# esp32.net
KiCad netlist of a schematic drawn in EAGLE
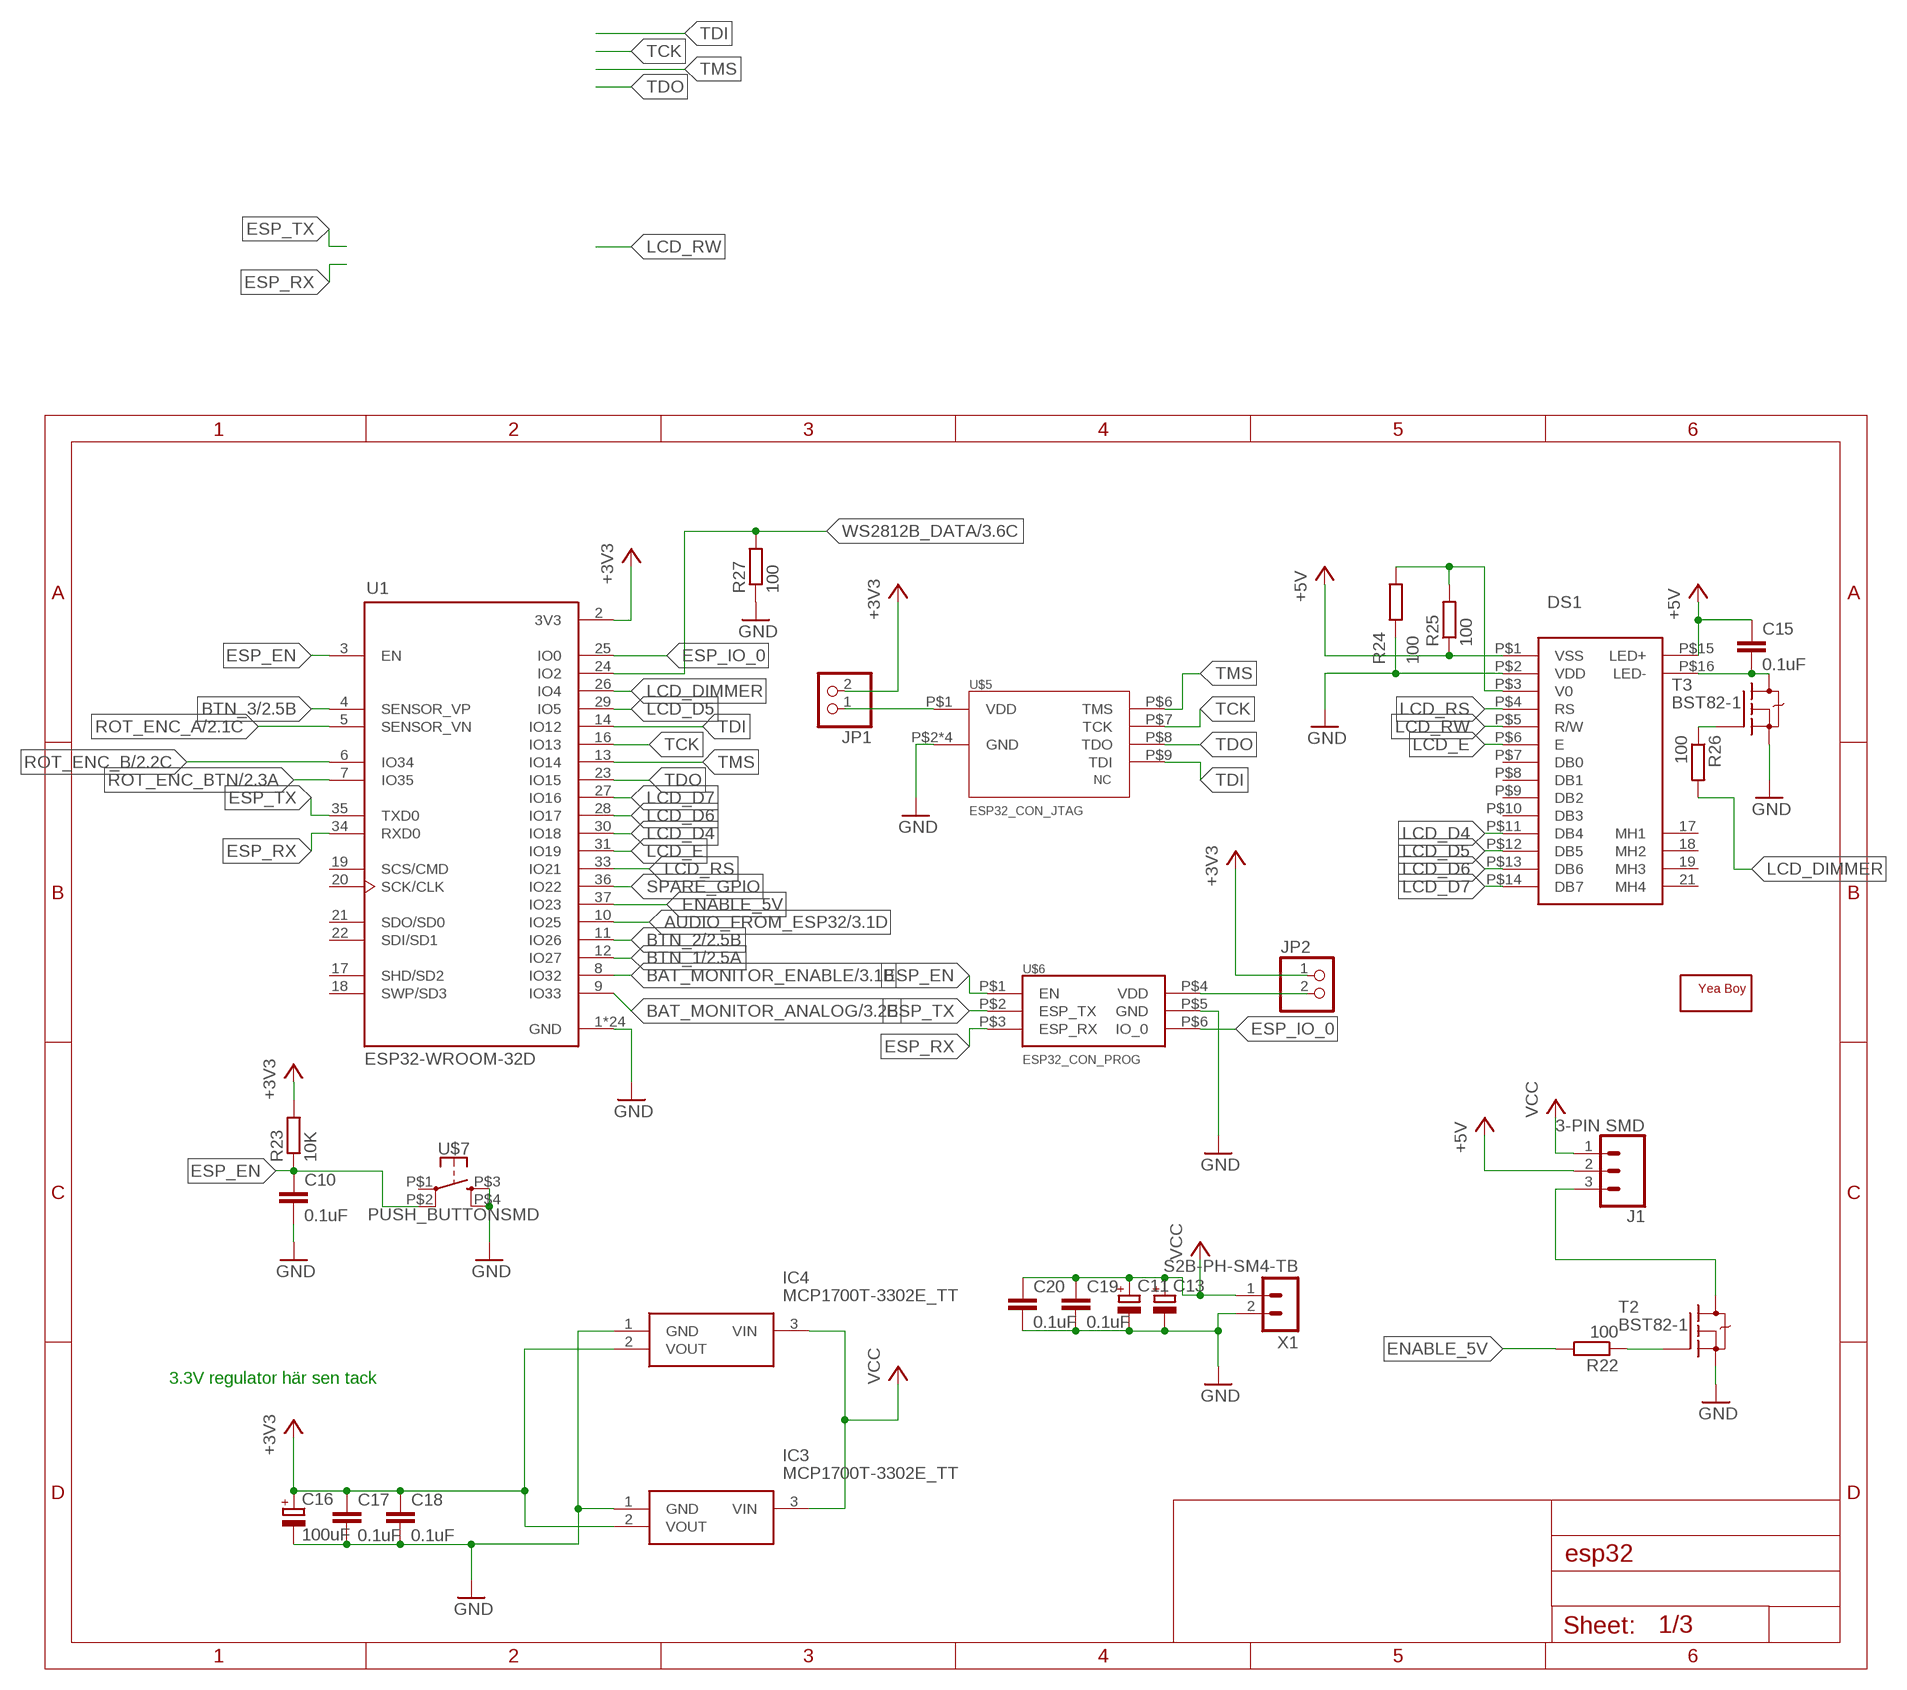
[diagram p0: schematic, sheet 1]
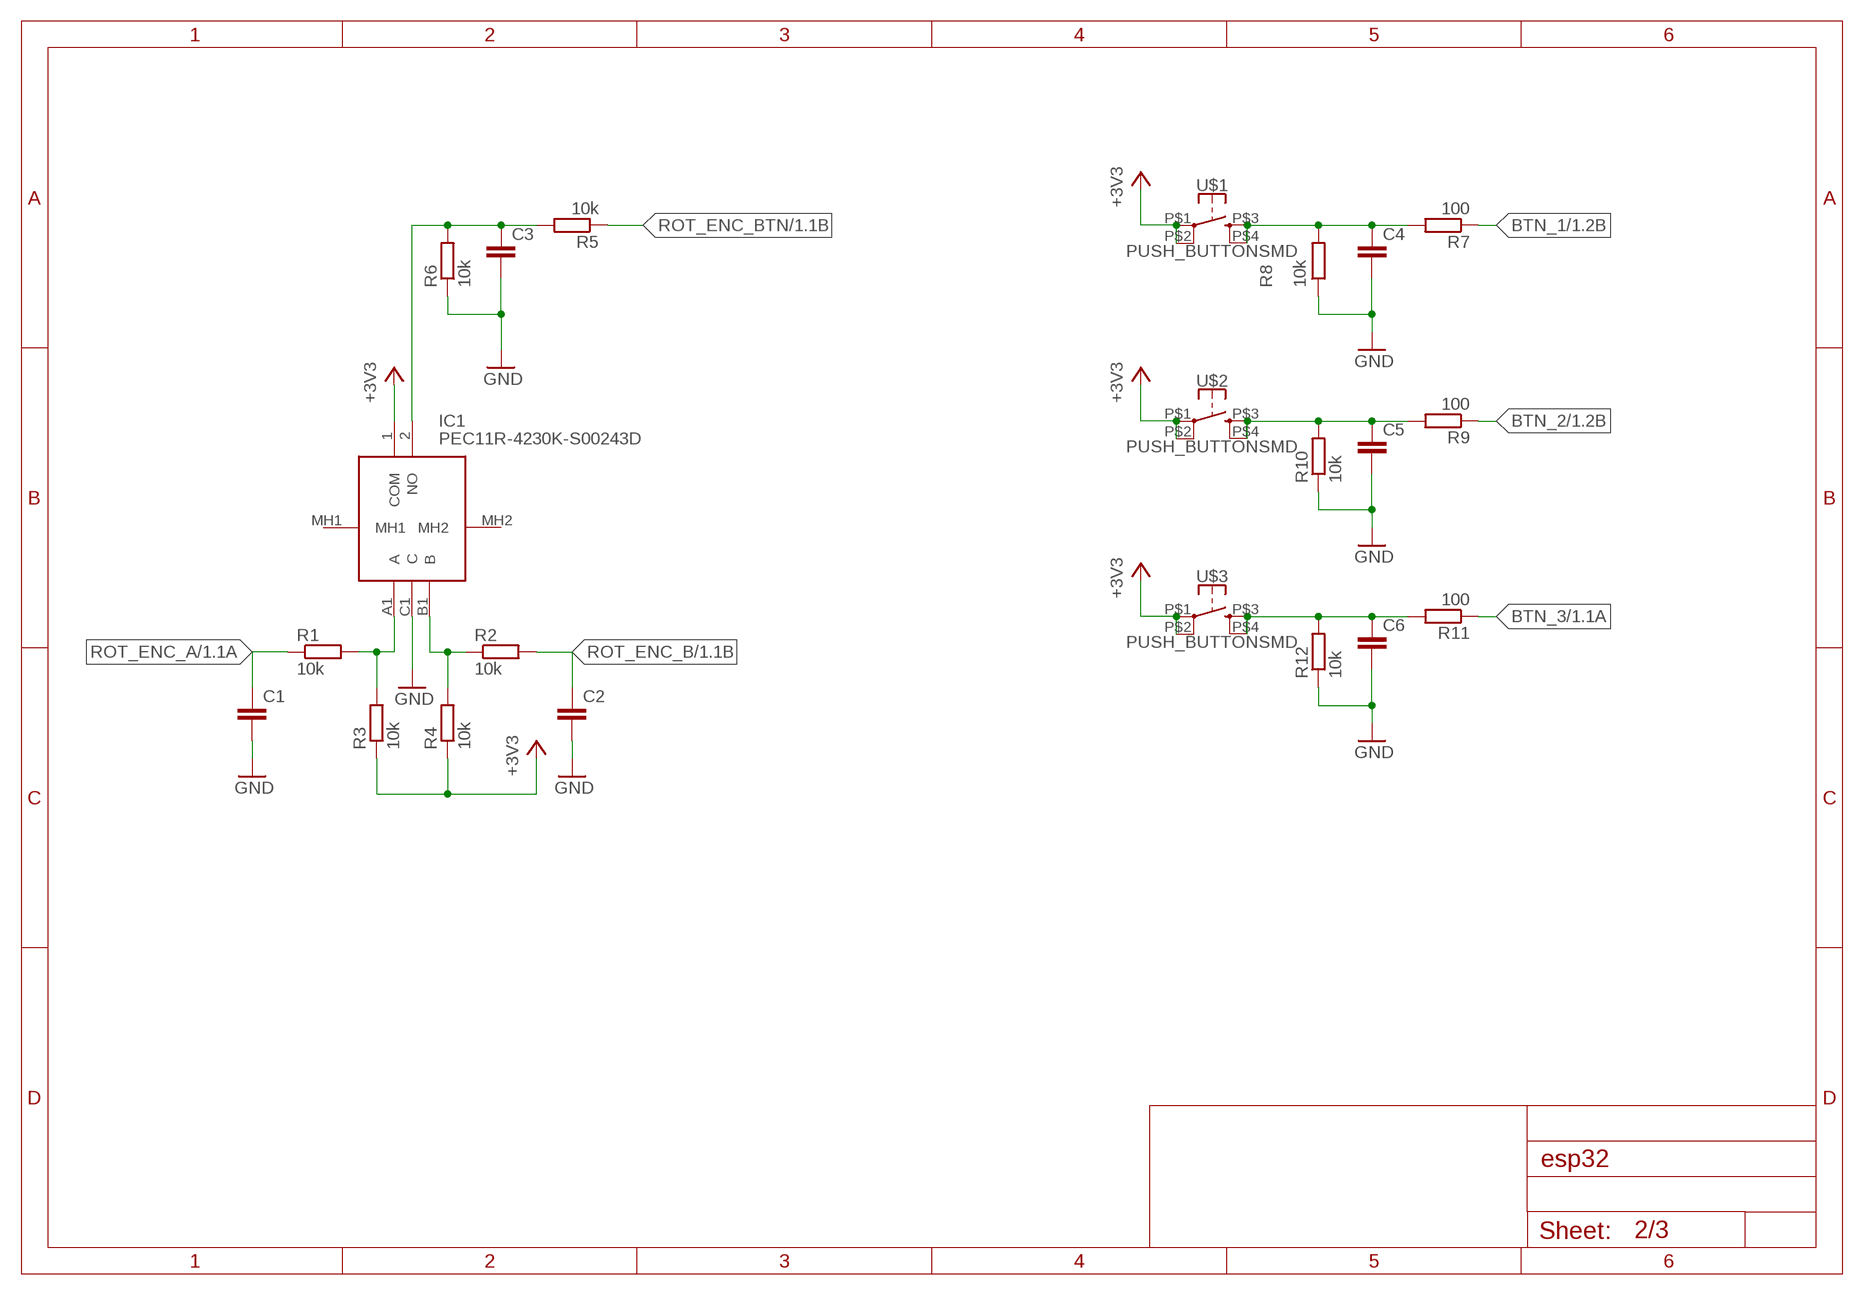
[diagram p1: schematic, sheet 2]
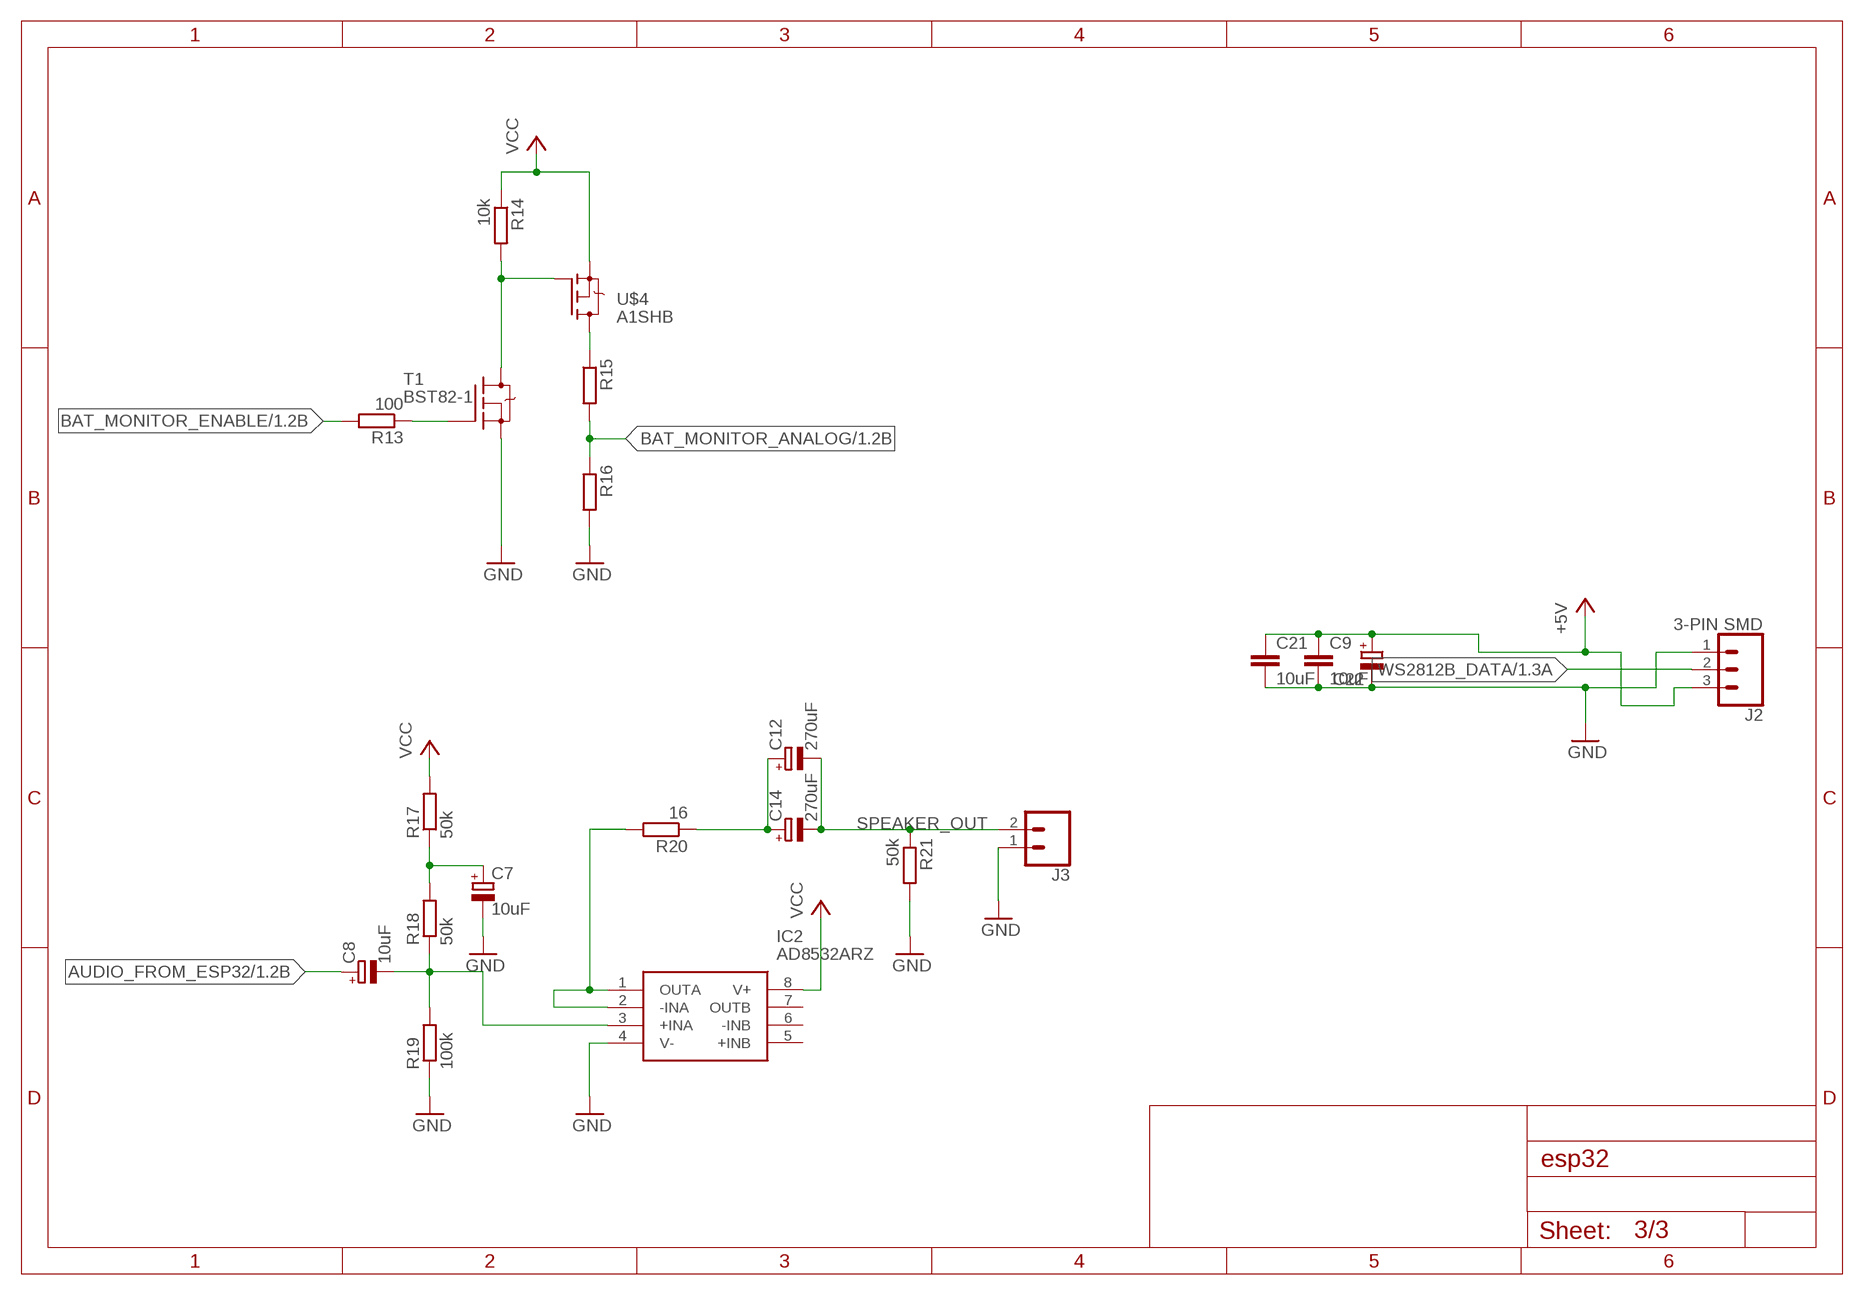
[diagram p2: schematic, sheet 3]

(export (version "E")
  (design (tool "Eeschema 10.0.6"))
  (components
    (comp (ref "C10")
      (value "0.1uF")
      (footprint "eagle-import:C0603")
      (libsource (lib "eagle-import") (part "C-EUC0603"))
    )
    (comp (ref "C11")
      (value "CPOL-EU153CLV-0605")
      (footprint "eagle-import:153CLV-0605")
      (libsource (lib "eagle-import") (part "CPOL-EU153CLV-0605"))
    )
    (comp (ref "C13")
      (value "CPOL-EU153CLV-0505")
      (footprint "eagle-import:153CLV-0505")
      (libsource (lib "eagle-import") (part "CPOL-EU153CLV-0505"))
    )
    (comp (ref "C15")
      (value "0.1uF")
      (footprint "eagle-import:C0603")
      (libsource (lib "eagle-import") (part "C-EUC0603"))
    )
    (comp (ref "C16")
      (value "100uF")
      (footprint "eagle-import:153CLV-0605")
      (libsource (lib "eagle-import") (part "CPOL-EU153CLV-0605"))
    )
    (comp (ref "C17")
      (value "0.1uF")
      (footprint "eagle-import:C0603")
      (libsource (lib "eagle-import") (part "C-EUC0603"))
    )
    (comp (ref "C18")
      (value "0.1uF")
      (footprint "eagle-import:C0603")
      (libsource (lib "eagle-import") (part "C-EUC0603"))
    )
    (comp (ref "C19")
      (value "0.1uF")
      (footprint "eagle-import:C0603")
      (libsource (lib "eagle-import") (part "C-EUC0603"))
    )
    (comp (ref "C20")
      (value "0.1uF")
      (footprint "eagle-import:C0603")
      (libsource (lib "eagle-import") (part "C-EUC0603"))
    )
    (comp (ref "DS1")
      (value "NHD-0216XZ-FSW-GBWSMT")
      (footprint "eagle-import:NHD0216XZFSWGBW_SMT")
      (libsource (lib "eagle-import") (part "NHD-0216XZ-FSW-GBWSMT"))
    )
    (comp (ref "IC3")
      (value "MCP1700T-3302E_TT")
      (footprint "eagle-import:SOT95P237X112-3N")
      (fields
        (field (name "MANUFACTURER_PART_NUMBER") "MCP1700T-3302E/TT")
        (field (name "MOUSER_PART_NUMBER") "579-MCP1700T3302E/TT")
      )
      (libsource (lib "eagle-import") (part "MCP1700T-3302E_TT"))
    )
    (comp (ref "IC4")
      (value "MCP1700T-3302E_TT")
      (footprint "eagle-import:SOT95P237X112-3N")
      (fields
        (field (name "MANUFACTURER_PART_NUMBER") "MCP1700T-3302E/TT")
        (field (name "MOUSER_PART_NUMBER") "579-MCP1700T3302E/TT")
      )
      (libsource (lib "eagle-import") (part "MCP1700T-3302E_TT"))
    )
    (comp (ref "J1")
      (value "3-PIN SMD")
      (footprint "eagle-import:JST-3-SMD")
      (libsource (lib "eagle-import") (part "CONN_03JST-SMD"))
    )
    (comp (ref "JP1")
      (value "PINHD-1X2")
      (footprint "eagle-import:1X02")
      (libsource (lib "eagle-import") (part "PINHD-1X2"))
    )
    (comp (ref "JP2")
      (value "PINHD-1X2")
      (footprint "eagle-import:1X02")
      (libsource (lib "eagle-import") (part "PINHD-1X2"))
    )
    (comp (ref "R22")
      (value "100")
      (footprint "eagle-import:R0603")
      (libsource (lib "eagle-import") (part "R-EU_R0603"))
    )
    (comp (ref "R23")
      (value "10K")
      (footprint "eagle-import:R0603")
      (libsource (lib "eagle-import") (part "R-EU_R0603"))
    )
    (comp (ref "R24")
      (value "100")
      (footprint "eagle-import:R0603")
      (libsource (lib "eagle-import") (part "R-EU_R0603"))
    )
    (comp (ref "R25")
      (value "100")
      (footprint "eagle-import:R0603")
      (libsource (lib "eagle-import") (part "R-EU_R0603"))
    )
    (comp (ref "R26")
      (value "100")
      (footprint "eagle-import:R0603")
      (libsource (lib "eagle-import") (part "R-EU_R0603"))
    )
    (comp (ref "R27")
      (value "100")
      (footprint "eagle-import:R0603")
      (libsource (lib "eagle-import") (part "R-EU_R0603"))
    )
    (comp (ref "T2")
      (value "BST82-1")
      (footprint "eagle-import:SOT23")
      (libsource (lib "eagle-import") (part "BST82-1"))
    )
    (comp (ref "T3")
      (value "BST82-1")
      (footprint "eagle-import:SOT23")
      (libsource (lib "eagle-import") (part "BST82-1"))
    )
    (comp (ref "U$5")
      (value "ESP32_CON_JTAG")
      (footprint "eagle-import:DC3_10P_0.05")
      (libsource (lib "eagle-import") (part "ESP32_CON_JTAG"))
    )
    (comp (ref "U$6")
      (value "ESP32_CON_PROG")
      (footprint "eagle-import:DC3_6P_0.05")
      (libsource (lib "eagle-import") (part "ESP32_CON_PROG"))
    )
    (comp (ref "U$7")
      (value "PUSH_BUTTONSMD")
      (footprint "eagle-import:TACTILE_SWITCH_PTH_6.0MM_SMD")
      (libsource (lib "eagle-import") (part "PUSH_BUTTONSMD"))
    )
    (comp (ref "U$8")
      (value "TOUCHMARK")
      (footprint "eagle-import:TOUCHMARK")
      (libsource (lib "eagle-import") (part "TOUCHMARK"))
    )
    (comp (ref "U1")
      (value "ESP32-WROOM-32D")
      (footprint "eagle-import:MODULE_ESP32-WROOM-32D")
      (fields (field (name "MANUFACTURER") "Espressif Systems"))
      (libsource (lib "eagle-import") (part "ESP32-WROOM-32D"))
    )
    (comp (ref "X1")
      (value "S2B-PH-SM4-TB")
      (footprint "eagle-import:S2B-PH-SM4-TB")
      (libsource (lib "eagle-import") (part "S2B-PH-SM4-TB"))
    )
    (comp (ref "C7")
      (value "10uF")
      (footprint "eagle-import:153CLV-0505")
      (libsource (lib "eagle-import") (part "CPOL-EU153CLV-0505"))
    )
    (comp (ref "C8")
      (value "10uF")
      (footprint "eagle-import:153CLV-0505")
      (libsource (lib "eagle-import") (part "CPOL-EU153CLV-0505"))
    )
    (comp (ref "C9")
      (value "10uF")
      (footprint "eagle-import:C0603")
      (libsource (lib "eagle-import") (part "C-EUC0603"))
    )
    (comp (ref "C12")
      (value "270uF")
      (footprint "eagle-import:153CLV-0605")
      (libsource (lib "eagle-import") (part "CPOL-EU153CLV-0605"))
    )
    (comp (ref "C14")
      (value "270uF")
      (footprint "eagle-import:153CLV-0605")
      (libsource (lib "eagle-import") (part "CPOL-EU153CLV-0605"))
    )
    (comp (ref "C21")
      (value "10uF")
      (footprint "eagle-import:C0603")
      (libsource (lib "eagle-import") (part "C-EUC0603"))
    )
    (comp (ref "C22")
      (value "CPOL-EU153CLV-0605")
      (footprint "eagle-import:153CLV-0605")
      (libsource (lib "eagle-import") (part "CPOL-EU153CLV-0605"))
    )
    (comp (ref "IC2")
      (value "AD8532ARZ")
      (footprint "eagle-import:SOIC127P600X175-8N")
      (fields (field (name "MOUSER_PART_NUMBER") "584-AD8532ARZ"))
      (libsource (lib "eagle-import") (part "AD8532ARZ"))
    )
    (comp (ref "J2")
      (value "3-PIN SMD")
      (footprint "eagle-import:JST-3-SMD")
      (libsource (lib "eagle-import") (part "CONN_03JST-SMD"))
    )
    (comp (ref "J3")
      (value "CONN_02-JST-2MM-SMT")
      (footprint "eagle-import:JST-2-SMD")
      (libsource (lib "eagle-import") (part "CONN_02-JST-2MM-SMT"))
    )
    (comp (ref "R13")
      (value "100")
      (footprint "eagle-import:R0603")
      (libsource (lib "eagle-import") (part "R-EU_R0603"))
    )
    (comp (ref "R14")
      (value "10k")
      (footprint "eagle-import:R0603")
      (libsource (lib "eagle-import") (part "R-EU_R0603"))
    )
    (comp (ref "R15")
      (value "R-EU_R0603")
      (footprint "eagle-import:R0603")
      (libsource (lib "eagle-import") (part "R-EU_R0603"))
    )
    (comp (ref "R16")
      (value "R-EU_R0603")
      (footprint "eagle-import:R0603")
      (libsource (lib "eagle-import") (part "R-EU_R0603"))
    )
    (comp (ref "R17")
      (value "50k")
      (footprint "eagle-import:R0603")
      (libsource (lib "eagle-import") (part "R-EU_R0603"))
    )
    (comp (ref "R18")
      (value "50k")
      (footprint "eagle-import:R0603")
      (libsource (lib "eagle-import") (part "R-EU_R0603"))
    )
    (comp (ref "R19")
      (value "100k")
      (footprint "eagle-import:R0603")
      (libsource (lib "eagle-import") (part "R-EU_R0603"))
    )
    (comp (ref "R20")
      (value "16")
      (footprint "eagle-import:R0603")
      (libsource (lib "eagle-import") (part "R-EU_R0603"))
    )
    (comp (ref "R21")
      (value "50k")
      (footprint "eagle-import:R0603")
      (libsource (lib "eagle-import") (part "R-EU_R0603"))
    )
    (comp (ref "T1")
      (value "BST82-1")
      (footprint "eagle-import:SOT23")
      (libsource (lib "eagle-import") (part "BST82-1"))
    )
    (comp (ref "U$4")
      (value "A1SHB")
      (footprint "eagle-import:SOT23")
      (libsource (lib "eagle-import") (part "A1SHB"))
    )
    (comp (ref "C1")
      (value "C-EUC0603")
      (footprint "eagle-import:C0603")
      (libsource (lib "eagle-import") (part "C-EUC0603"))
    )
    (comp (ref "C2")
      (value "C-EUC0603")
      (footprint "eagle-import:C0603")
      (libsource (lib "eagle-import") (part "C-EUC0603"))
    )
    (comp (ref "C3")
      (value "C-EUC0603")
      (footprint "eagle-import:C0603")
      (libsource (lib "eagle-import") (part "C-EUC0603"))
    )
    (comp (ref "C4")
      (value "C-EUC0603")
      (footprint "eagle-import:C0603")
      (libsource (lib "eagle-import") (part "C-EUC0603"))
    )
    (comp (ref "C5")
      (value "C-EUC0603")
      (footprint "eagle-import:C0603")
      (libsource (lib "eagle-import") (part "C-EUC0603"))
    )
    (comp (ref "C6")
      (value "C-EUC0603")
      (footprint "eagle-import:C0603")
      (libsource (lib "eagle-import") (part "C-EUC0603"))
    )
    (comp (ref "IC1")
      (value "PEC11R-4230K-S00243D")
      (footprint "eagle-import:PEC11R4230KS0024")
      (libsource (lib "eagle-import") (part "PEC11R-4230K-S00243D"))
    )
    (comp (ref "R1")
      (value "10k")
      (footprint "eagle-import:R0603")
      (libsource (lib "eagle-import") (part "R-EU_R0603"))
    )
    (comp (ref "R2")
      (value "10k")
      (footprint "eagle-import:R0603")
      (libsource (lib "eagle-import") (part "R-EU_R0603"))
    )
    (comp (ref "R3")
      (value "10k")
      (footprint "eagle-import:R0603")
      (libsource (lib "eagle-import") (part "R-EU_R0603"))
    )
    (comp (ref "R4")
      (value "10k")
      (footprint "eagle-import:R0603")
      (libsource (lib "eagle-import") (part "R-EU_R0603"))
    )
    (comp (ref "R5")
      (value "10k")
      (footprint "eagle-import:R0603")
      (libsource (lib "eagle-import") (part "R-EU_R0603"))
    )
    (comp (ref "R6")
      (value "10k")
      (footprint "eagle-import:R0603")
      (libsource (lib "eagle-import") (part "R-EU_R0603"))
    )
    (comp (ref "R7")
      (value "100")
      (footprint "eagle-import:R0603")
      (libsource (lib "eagle-import") (part "R-EU_R0603"))
    )
    (comp (ref "R8")
      (value "10k")
      (footprint "eagle-import:R0603")
      (libsource (lib "eagle-import") (part "R-EU_R0603"))
    )
    (comp (ref "R9")
      (value "100")
      (footprint "eagle-import:R0603")
      (libsource (lib "eagle-import") (part "R-EU_R0603"))
    )
    (comp (ref "R10")
      (value "10k")
      (footprint "eagle-import:R0603")
      (libsource (lib "eagle-import") (part "R-EU_R0603"))
    )
    (comp (ref "R11")
      (value "100")
      (footprint "eagle-import:R0603")
      (libsource (lib "eagle-import") (part "R-EU_R0603"))
    )
    (comp (ref "R12")
      (value "10k")
      (footprint "eagle-import:R0603")
      (libsource (lib "eagle-import") (part "R-EU_R0603"))
    )
    (comp (ref "U$1")
      (value "PUSH_BUTTONSMD")
      (footprint "eagle-import:TACTILE_SWITCH_PTH_6.0MM_SMD")
      (libsource (lib "eagle-import") (part "PUSH_BUTTONSMD"))
    )
    (comp (ref "U$2")
      (value "PUSH_BUTTONSMD")
      (footprint "eagle-import:TACTILE_SWITCH_PTH_6.0MM_SMD")
      (libsource (lib "eagle-import") (part "PUSH_BUTTONSMD"))
    )
    (comp (ref "U$3")
      (value "PUSH_BUTTONSMD")
      (footprint "eagle-import:TACTILE_SWITCH_PTH_6.0MM_SMD")
      (libsource (lib "eagle-import") (part "PUSH_BUTTONSMD"))
    )
  )
  (nets
    (net (code "1") (name "+3V3") (class "Default")
      (node (ref "C16") (pin "+") (pinfunction "+_+") (pintype "passive"))
      (node (ref "C17") (pin "1") (pinfunction "1_1") (pintype "passive"))
      (node (ref "C18") (pin "1") (pinfunction "1_1") (pintype "passive"))
      (node (ref "IC1") (pin "1") (pinfunction "COM_1") (pintype "bidirectional"))
      (node (ref "IC3") (pin "2") (pinfunction "VOUT_2") (pintype "bidirectional"))
      (node (ref "IC4") (pin "2") (pinfunction "VOUT_2") (pintype "bidirectional"))
      (node (ref "JP1") (pin "2") (pinfunction "2_2") (pintype "passive"))
      (node (ref "JP2") (pin "1") (pinfunction "1_1") (pintype "passive"))
      (node (ref "R23") (pin "2") (pinfunction "2_2") (pintype "passive"))
      (node (ref "R3") (pin "1") (pinfunction "1_1") (pintype "passive"))
      (node (ref "R4") (pin "1") (pinfunction "1_1") (pintype "passive"))
      (node (ref "U$1") (pin "P$1") (pinfunction "1_P$1") (pintype "passive"))
      (node (ref "U$1") (pin "P$2") (pinfunction "2_P$2") (pintype "passive"))
      (node (ref "U$2") (pin "P$1") (pinfunction "1_P$1") (pintype "passive"))
      (node (ref "U$2") (pin "P$2") (pinfunction "2_P$2") (pintype "passive"))
      (node (ref "U$3") (pin "P$1") (pinfunction "1_P$1") (pintype "passive"))
      (node (ref "U$3") (pin "P$2") (pinfunction "2_P$2") (pintype "passive"))
      (node (ref "U1") (pin "2") (pinfunction "3V3_2") (pintype "power_in"))
    )
    (net (code "2") (name "+5V") (class "Default")
      (node (ref "C15") (pin "1") (pinfunction "1_1") (pintype "passive"))
      (node (ref "C21") (pin "1") (pinfunction "1_1") (pintype "passive"))
      (node (ref "C22") (pin "+") (pinfunction "+_+") (pintype "passive"))
      (node (ref "C9") (pin "1") (pinfunction "1_1") (pintype "passive"))
      (node (ref "DS1") (pin "P$1") (pinfunction "VSS_P$1") (pintype "bidirectional"))
      (node (ref "DS1") (pin "P$15") (pinfunction "LED+_P$15") (pintype "bidirectional"))
      (node (ref "J1") (pin "2") (pinfunction "2_2") (pintype "passive"))
      (node (ref "J2") (pin "3") (pinfunction "3_3") (pintype "passive"))
      (node (ref "R25") (pin "1") (pinfunction "1_1") (pintype "passive"))
    )
    (net (code "3") (name "AUDIO_FROM_ESP32") (class "Default")
      (node (ref "C8") (pin "+") (pinfunction "+_+") (pintype "passive"))
      (node (ref "U1") (pin "10") (pinfunction "IO25_10") (pintype "bidirectional"))
    )
    (net (code "4") (name "BAT_MONITOR_ANALOG") (class "Default")
      (node (ref "R15") (pin "2") (pinfunction "2_2") (pintype "passive"))
      (node (ref "R16") (pin "1") (pinfunction "1_1") (pintype "passive"))
      (node (ref "U1") (pin "9") (pinfunction "IO33_9") (pintype "bidirectional"))
    )
    (net (code "5") (name "BAT_MONITOR_ENABLE") (class "Default")
      (node (ref "R13") (pin "2") (pinfunction "2_2") (pintype "passive"))
      (node (ref "U1") (pin "8") (pinfunction "IO32_8") (pintype "bidirectional"))
    )
    (net (code "6") (name "BTN_1") (class "Default")
      (node (ref "R7") (pin "1") (pinfunction "1_1") (pintype "passive"))
      (node (ref "U1") (pin "12") (pinfunction "IO27_12") (pintype "bidirectional"))
    )
    (net (code "7") (name "BTN_2") (class "Default")
      (node (ref "R9") (pin "1") (pinfunction "1_1") (pintype "passive"))
      (node (ref "U1") (pin "11") (pinfunction "IO26_11") (pintype "bidirectional"))
    )
    (net (code "8") (name "BTN_3") (class "Default")
      (node (ref "R11") (pin "1") (pinfunction "1_1") (pintype "passive"))
      (node (ref "U1") (pin "4") (pinfunction "SENSOR_VP_4") (pintype "input"))
    )
    (net (code "9") (name "ENABLE_5V") (class "Default")
      (node (ref "R22") (pin "2") (pinfunction "2_2") (pintype "passive"))
      (node (ref "U1") (pin "37") (pinfunction "IO23_37") (pintype "bidirectional"))
    )
    (net (code "10") (name "ESP_EN") (class "Default")
      (node (ref "C10") (pin "1") (pinfunction "1_1") (pintype "passive"))
      (node (ref "R23") (pin "1") (pinfunction "1_1") (pintype "passive"))
      (node (ref "U$6") (pin "P$1") (pinfunction "EN_P$1") (pintype "bidirectional"))
      (node (ref "U$7") (pin "P$2") (pinfunction "2_P$2") (pintype "passive"))
      (node (ref "U1") (pin "3") (pinfunction "EN_3") (pintype "input"))
    )
    (net (code "11") (name "ESP_IO_0") (class "Default")
      (node (ref "U$6") (pin "P$6") (pinfunction "IO_0_P$6") (pintype "bidirectional"))
      (node (ref "U1") (pin "25") (pinfunction "IO0_25") (pintype "bidirectional"))
    )
    (net (code "12") (name "ESP_RX") (class "Default")
      (node (ref "U$6") (pin "P$3") (pinfunction "ESP_RX_P$3") (pintype "bidirectional"))
      (node (ref "U1") (pin "34") (pinfunction "RXD0_34") (pintype "bidirectional"))
    )
    (net (code "13") (name "ESP_TX") (class "Default")
      (node (ref "U$6") (pin "P$2") (pinfunction "ESP_TX_P$2") (pintype "bidirectional"))
      (node (ref "U1") (pin "35") (pinfunction "TXD0_35") (pintype "bidirectional"))
    )
    (net (code "14") (name "GND") (class "Default")
      (node (ref "C1") (pin "2") (pinfunction "2_2") (pintype "passive"))
      (node (ref "C10") (pin "2") (pinfunction "2_2") (pintype "passive"))
      (node (ref "C11") (pin "-") (pinfunction "-_-") (pintype "passive"))
      (node (ref "C13") (pin "-") (pinfunction "-_-") (pintype "passive"))
      (node (ref "C16") (pin "-") (pinfunction "-_-") (pintype "passive"))
      (node (ref "C17") (pin "2") (pinfunction "2_2") (pintype "passive"))
      (node (ref "C18") (pin "2") (pinfunction "2_2") (pintype "passive"))
      (node (ref "C19") (pin "2") (pinfunction "2_2") (pintype "passive"))
      (node (ref "C2") (pin "2") (pinfunction "2_2") (pintype "passive"))
      (node (ref "C20") (pin "2") (pinfunction "2_2") (pintype "passive"))
      (node (ref "C21") (pin "2") (pinfunction "2_2") (pintype "passive"))
      (node (ref "C22") (pin "-") (pinfunction "-_-") (pintype "passive"))
      (node (ref "C3") (pin "2") (pinfunction "2_2") (pintype "passive"))
      (node (ref "C4") (pin "2") (pinfunction "2_2") (pintype "passive"))
      (node (ref "C5") (pin "2") (pinfunction "2_2") (pintype "passive"))
      (node (ref "C6") (pin "2") (pinfunction "2_2") (pintype "passive"))
      (node (ref "C7") (pin "-") (pinfunction "-_-") (pintype "passive"))
      (node (ref "C9") (pin "2") (pinfunction "2_2") (pintype "passive"))
      (node (ref "DS1") (pin "P$2") (pinfunction "VDD_P$2") (pintype "bidirectional"))
      (node (ref "IC1") (pin "C1") (pinfunction "C_C1") (pintype "bidirectional"))
      (node (ref "IC2") (pin "4") (pinfunction "V-_4") (pintype "bidirectional"))
      (node (ref "IC3") (pin "1") (pinfunction "GND_1") (pintype "bidirectional"))
      (node (ref "IC4") (pin "1") (pinfunction "GND_1") (pintype "bidirectional"))
      (node (ref "J2") (pin "1") (pinfunction "1_1") (pintype "passive"))
      (node (ref "J3") (pin "1") (pinfunction "2_1") (pintype "passive"))
      (node (ref "R10") (pin "1") (pinfunction "1_1") (pintype "passive"))
      (node (ref "R12") (pin "1") (pinfunction "1_1") (pintype "passive"))
      (node (ref "R16") (pin "2") (pinfunction "2_2") (pintype "passive"))
      (node (ref "R19") (pin "1") (pinfunction "1_1") (pintype "passive"))
      (node (ref "R21") (pin "2") (pinfunction "2_2") (pintype "passive"))
      (node (ref "R24") (pin "1") (pinfunction "1_1") (pintype "passive"))
      (node (ref "R27") (pin "1") (pinfunction "1_1") (pintype "passive"))
      (node (ref "R6") (pin "1") (pinfunction "1_1") (pintype "passive"))
      (node (ref "R8") (pin "1") (pinfunction "1_1") (pintype "passive"))
      (node (ref "T1") (pin "2") (pinfunction "S_2") (pintype "passive"))
      (node (ref "T2") (pin "2") (pinfunction "S_2") (pintype "passive"))
      (node (ref "T3") (pin "2") (pinfunction "S_2") (pintype "passive"))
      (node (ref "U$5") (pin "P$2") (pinfunction "GND_P$2") (pintype "bidirectional"))
      (node (ref "U$5") (pin "P$3") (pinfunction "GND_P$3") (pintype "bidirectional"))
      (node (ref "U$5") (pin "P$4") (pinfunction "GND_P$4") (pintype "bidirectional"))
      (node (ref "U$5") (pin "P$5") (pinfunction "GND_P$5") (pintype "bidirectional"))
      (node (ref "U$6") (pin "P$5") (pinfunction "GND_P$5") (pintype "bidirectional"))
      (node (ref "U$7") (pin "P$3") (pinfunction "3_P$3") (pintype "passive"))
      (node (ref "U$7") (pin "P$4") (pinfunction "4_P$4") (pintype "passive"))
      (node (ref "U1") (pin "1") (pinfunction "GND_1") (pintype "power_in"))
      (node (ref "U1") (pin "15") (pinfunction "GND_15") (pintype "power_in"))
      (node (ref "U1") (pin "38") (pinfunction "GND_38") (pintype "power_in"))
      (node (ref "U1") (pin "39_1") (pinfunction "GND_39_1") (pintype "power_in"))
      (node (ref "U1") (pin "39_10") (pinfunction "GND_39_10") (pintype "power_in"))
      (node (ref "U1") (pin "39_11") (pinfunction "GND_39_11") (pintype "power_in"))
      (node (ref "U1") (pin "39_12") (pinfunction "GND_39_12") (pintype "power_in"))
      (node (ref "U1") (pin "39_13") (pinfunction "GND_39_13") (pintype "power_in"))
      (node (ref "U1") (pin "39_14") (pinfunction "GND_39_14") (pintype "power_in"))
      (node (ref "U1") (pin "39_15") (pinfunction "GND_39_15") (pintype "power_in"))
      (node (ref "U1") (pin "39_16") (pinfunction "GND_39_16") (pintype "power_in"))
      (node (ref "U1") (pin "39_17") (pinfunction "GND_39_17") (pintype "power_in"))
      (node (ref "U1") (pin "39_18") (pinfunction "GND_39_18") (pintype "power_in"))
      (node (ref "U1") (pin "39_19") (pinfunction "GND_39_19") (pintype "power_in"))
      (node (ref "U1") (pin "39_2") (pinfunction "GND_39_2") (pintype "power_in"))
      (node (ref "U1") (pin "39_20") (pinfunction "GND_39_20") (pintype "power_in"))
      (node (ref "U1") (pin "39_21") (pinfunction "GND_39_21") (pintype "power_in"))
      (node (ref "U1") (pin "39_3") (pinfunction "GND_39_3") (pintype "power_in"))
      (node (ref "U1") (pin "39_4") (pinfunction "GND_39_4") (pintype "power_in"))
      (node (ref "U1") (pin "39_5") (pinfunction "GND_39_5") (pintype "power_in"))
      (node (ref "U1") (pin "39_6") (pinfunction "GND_39_6") (pintype "power_in"))
      (node (ref "U1") (pin "39_7") (pinfunction "GND_39_7") (pintype "power_in"))
      (node (ref "U1") (pin "39_8") (pinfunction "GND_39_8") (pintype "power_in"))
      (node (ref "U1") (pin "39_9") (pinfunction "GND_39_9") (pintype "power_in"))
      (node (ref "X1") (pin "2") (pinfunction "2_2") (pintype "passive"))
    )
    (net (code "15") (name "LCD_D4") (class "Default")
      (node (ref "DS1") (pin "P$11") (pinfunction "DB4_P$11") (pintype "bidirectional"))
      (node (ref "U1") (pin "30") (pinfunction "IO18_30") (pintype "bidirectional"))
    )
    (net (code "16") (name "LCD_D5") (class "Default")
      (node (ref "DS1") (pin "P$12") (pinfunction "DB5_P$12") (pintype "bidirectional"))
      (node (ref "U1") (pin "29") (pinfunction "IO5_29") (pintype "bidirectional"))
    )
    (net (code "17") (name "LCD_D6") (class "Default")
      (node (ref "DS1") (pin "P$13") (pinfunction "DB6_P$13") (pintype "bidirectional"))
      (node (ref "U1") (pin "28") (pinfunction "IO17_28") (pintype "bidirectional"))
    )
    (net (code "18") (name "LCD_D7") (class "Default")
      (node (ref "DS1") (pin "P$14") (pinfunction "DB7_P$14") (pintype "bidirectional"))
      (node (ref "U1") (pin "27") (pinfunction "IO16_27") (pintype "bidirectional"))
    )
    (net (code "19") (name "LCD_DIMMER") (class "Default")
      (node (ref "R26") (pin "2") (pinfunction "2_2") (pintype "passive"))
      (node (ref "U1") (pin "26") (pinfunction "IO4_26") (pintype "bidirectional"))
    )
    (net (code "20") (name "LCD_E") (class "Default")
      (node (ref "DS1") (pin "P$6") (pinfunction "E_P$6") (pintype "bidirectional"))
      (node (ref "U1") (pin "31") (pinfunction "IO19_31") (pintype "bidirectional"))
    )
    (net (code "21") (name "LCD_RS") (class "Default")
      (node (ref "DS1") (pin "P$4") (pinfunction "RS_P$4") (pintype "bidirectional"))
      (node (ref "U1") (pin "33") (pinfunction "IO21_33") (pintype "bidirectional"))
    )
    (net (code "22") (name "LCD_RW") (class "Default")
      (node (ref "DS1") (pin "P$5") (pinfunction "R/W_P$5") (pintype "bidirectional"))
    )
    (net (code "23") (name "Net-(C7-Pad+)") (class "Default")
      (node (ref "C7") (pin "+") (pinfunction "+_+") (pintype "passive"))
      (node (ref "R17") (pin "1") (pinfunction "1_1") (pintype "passive"))
      (node (ref "R18") (pin "2") (pinfunction "2_2") (pintype "passive"))
    )
    (net (code "24") (name "Net-(C12-Pad+)") (class "Default")
      (node (ref "C12") (pin "+") (pinfunction "+_+") (pintype "passive"))
      (node (ref "C14") (pin "+") (pinfunction "+_+") (pintype "passive"))
      (node (ref "R20") (pin "1") (pinfunction "1_1") (pintype "passive"))
    )
    (net (code "25") (name "Net-(DS1-LED-)") (class "Default")
      (node (ref "C15") (pin "2") (pinfunction "2_2") (pintype "passive"))
      (node (ref "DS1") (pin "P$16") (pinfunction "LED-_P$16") (pintype "bidirectional"))
      (node (ref "T3") (pin "3") (pinfunction "D_3") (pintype "passive"))
    )
    (net (code "26") (name "Net-(DS1-V0)") (class "Default")
      (node (ref "DS1") (pin "P$3") (pinfunction "V0_P$3") (pintype "bidirectional"))
      (node (ref "R24") (pin "2") (pinfunction "2_2") (pintype "passive"))
      (node (ref "R25") (pin "2") (pinfunction "2_2") (pintype "passive"))
    )
    (net (code "27") (name "Net-(IC1-A)") (class "Default")
      (node (ref "IC1") (pin "A1") (pinfunction "A_A1") (pintype "bidirectional"))
      (node (ref "R1") (pin "2") (pinfunction "2_2") (pintype "passive"))
      (node (ref "R3") (pin "2") (pinfunction "2_2") (pintype "passive"))
    )
    (net (code "28") (name "Net-(IC1-B)") (class "Default")
      (node (ref "IC1") (pin "B1") (pinfunction "B_B1") (pintype "bidirectional"))
      (node (ref "R2") (pin "1") (pinfunction "1_1") (pintype "passive"))
      (node (ref "R4") (pin "2") (pinfunction "2_2") (pintype "passive"))
    )
    (net (code "29") (name "Net-(IC1-NO)") (class "Default")
      (node (ref "C3") (pin "1") (pinfunction "1_1") (pintype "passive"))
      (node (ref "IC1") (pin "2") (pinfunction "NO_2") (pintype "bidirectional"))
      (node (ref "R5") (pin "2") (pinfunction "2_2") (pintype "passive"))
      (node (ref "R6") (pin "2") (pinfunction "2_2") (pintype "passive"))
    )
    (net (code "30") (name "Net-(IC2-+INA)") (class "Default")
      (node (ref "C8") (pin "-") (pinfunction "-_-") (pintype "passive"))
      (node (ref "IC2") (pin "3") (pinfunction "+INA_3") (pintype "bidirectional"))
      (node (ref "R18") (pin "1") (pinfunction "1_1") (pintype "passive"))
      (node (ref "R19") (pin "2") (pinfunction "2_2") (pintype "passive"))
    )
    (net (code "31") (name "Net-(IC2--INA)") (class "Default")
      (node (ref "IC2") (pin "1") (pinfunction "OUTA_1") (pintype "bidirectional"))
      (node (ref "IC2") (pin "2") (pinfunction "-INA_2") (pintype "bidirectional"))
      (node (ref "R20") (pin "2") (pinfunction "2_2") (pintype "passive"))
    )
    (net (code "32") (name "Net-(T1-D)") (class "Default")
      (node (ref "R14") (pin "2") (pinfunction "2_2") (pintype "passive"))
      (node (ref "T1") (pin "3") (pinfunction "D_3") (pintype "passive"))
      (node (ref "U$4") (pin "1") (pinfunction "G_1") (pintype "passive"))
    )
    (net (code "33") (name "Net-(T1-G)") (class "Default")
      (node (ref "R13") (pin "1") (pinfunction "1_1") (pintype "passive"))
      (node (ref "T1") (pin "1") (pinfunction "G_1") (pintype "passive"))
    )
    (net (code "34") (name "Net-(T2-D)") (class "Default")
      (node (ref "J1") (pin "3") (pinfunction "3_3") (pintype "passive"))
      (node (ref "T2") (pin "3") (pinfunction "D_3") (pintype "passive"))
    )
    (net (code "35") (name "Net-(T2-G)") (class "Default")
      (node (ref "R22") (pin "1") (pinfunction "1_1") (pintype "passive"))
      (node (ref "T2") (pin "1") (pinfunction "G_1") (pintype "passive"))
    )
    (net (code "36") (name "Net-(T3-G)") (class "Default")
      (node (ref "R26") (pin "1") (pinfunction "1_1") (pintype "passive"))
      (node (ref "T3") (pin "1") (pinfunction "G_1") (pintype "passive"))
    )
    (net (code "37") (name "Net-(U$1-3)") (class "Default")
      (node (ref "C4") (pin "1") (pinfunction "1_1") (pintype "passive"))
      (node (ref "R7") (pin "2") (pinfunction "2_2") (pintype "passive"))
      (node (ref "R8") (pin "2") (pinfunction "2_2") (pintype "passive"))
      (node (ref "U$1") (pin "P$3") (pinfunction "3_P$3") (pintype "passive"))
      (node (ref "U$1") (pin "P$4") (pinfunction "4_P$4") (pintype "passive"))
    )
    (net (code "38") (name "Net-(U$2-3)") (class "Default")
      (node (ref "C5") (pin "1") (pinfunction "1_1") (pintype "passive"))
      (node (ref "R10") (pin "2") (pinfunction "2_2") (pintype "passive"))
      (node (ref "R9") (pin "2") (pinfunction "2_2") (pintype "passive"))
      (node (ref "U$2") (pin "P$3") (pinfunction "3_P$3") (pintype "passive"))
      (node (ref "U$2") (pin "P$4") (pinfunction "4_P$4") (pintype "passive"))
    )
    (net (code "39") (name "Net-(U$3-3)") (class "Default")
      (node (ref "C6") (pin "1") (pinfunction "1_1") (pintype "passive"))
      (node (ref "R11") (pin "2") (pinfunction "2_2") (pintype "passive"))
      (node (ref "R12") (pin "2") (pinfunction "2_2") (pintype "passive"))
      (node (ref "U$3") (pin "P$3") (pinfunction "3_P$3") (pintype "passive"))
      (node (ref "U$3") (pin "P$4") (pinfunction "4_P$4") (pintype "passive"))
    )
    (net (code "40") (name "Net-(U$4-D)") (class "Default")
      (node (ref "R15") (pin "1") (pinfunction "1_1") (pintype "passive"))
      (node (ref "U$4") (pin "3") (pinfunction "D_3") (pintype "passive"))
    )
    (net (code "41") (name "Net-(U$5-VDD)") (class "Default")
      (node (ref "JP1") (pin "1") (pinfunction "1_1") (pintype "passive"))
      (node (ref "U$5") (pin "P$1") (pinfunction "VDD_P$1") (pintype "bidirectional"))
    )
    (net (code "42") (name "Net-(U$6-VDD)") (class "Default")
      (node (ref "JP2") (pin "2") (pinfunction "2_2") (pintype "passive"))
      (node (ref "U$6") (pin "P$4") (pinfunction "VDD_P$4") (pintype "bidirectional"))
    )
    (net (code "43") (name "ROT_ENC_A") (class "Default")
      (node (ref "C1") (pin "1") (pinfunction "1_1") (pintype "passive"))
      (node (ref "R1") (pin "1") (pinfunction "1_1") (pintype "passive"))
      (node (ref "U1") (pin "5") (pinfunction "SENSOR_VN_5") (pintype "input"))
    )
    (net (code "44") (name "ROT_ENC_B") (class "Default")
      (node (ref "C2") (pin "1") (pinfunction "1_1") (pintype "passive"))
      (node (ref "R2") (pin "2") (pinfunction "2_2") (pintype "passive"))
      (node (ref "U1") (pin "6") (pinfunction "IO34_6") (pintype "input"))
    )
    (net (code "45") (name "ROT_ENC_BTN") (class "Default")
      (node (ref "R5") (pin "1") (pinfunction "1_1") (pintype "passive"))
      (node (ref "U1") (pin "7") (pinfunction "IO35_7") (pintype "input"))
    )
    (net (code "46") (name "SPARE_GPIO") (class "Default")
      (node (ref "U1") (pin "36") (pinfunction "IO22_36") (pintype "bidirectional"))
    )
    (net (code "47") (name "SPEAKER_OUT") (class "Default")
      (node (ref "C12") (pin "-") (pinfunction "-_-") (pintype "passive"))
      (node (ref "C14") (pin "-") (pinfunction "-_-") (pintype "passive"))
      (node (ref "J3") (pin "2") (pinfunction "1_2") (pintype "passive"))
      (node (ref "R21") (pin "1") (pinfunction "1_1") (pintype "passive"))
    )
    (net (code "48") (name "TCK") (class "Default")
      (node (ref "U$5") (pin "P$7") (pinfunction "TCK_P$7") (pintype "bidirectional"))
      (node (ref "U1") (pin "16") (pinfunction "IO13_16") (pintype "bidirectional"))
    )
    (net (code "49") (name "TDI") (class "Default")
      (node (ref "U$5") (pin "P$9") (pinfunction "TDI_P$9") (pintype "bidirectional"))
      (node (ref "U1") (pin "14") (pinfunction "IO12_14") (pintype "bidirectional"))
    )
    (net (code "50") (name "TDO") (class "Default")
      (node (ref "U$5") (pin "P$8") (pinfunction "TDO_P$8") (pintype "bidirectional"))
      (node (ref "U1") (pin "23") (pinfunction "IO15_23") (pintype "bidirectional"))
    )
    (net (code "51") (name "TMS") (class "Default")
      (node (ref "U$5") (pin "P$6") (pinfunction "TMS_P$6") (pintype "bidirectional"))
      (node (ref "U1") (pin "13") (pinfunction "IO14_13") (pintype "bidirectional"))
    )
    (net (code "52") (name "VCC") (class "Default")
      (node (ref "C11") (pin "+") (pinfunction "+_+") (pintype "passive"))
      (node (ref "C13") (pin "+") (pinfunction "+_+") (pintype "passive"))
      (node (ref "C19") (pin "1") (pinfunction "1_1") (pintype "passive"))
      (node (ref "C20") (pin "1") (pinfunction "1_1") (pintype "passive"))
      (node (ref "IC2") (pin "8") (pinfunction "V+_8") (pintype "bidirectional"))
      (node (ref "IC3") (pin "3") (pinfunction "VIN_3") (pintype "bidirectional"))
      (node (ref "IC4") (pin "3") (pinfunction "VIN_3") (pintype "bidirectional"))
      (node (ref "J1") (pin "1") (pinfunction "1_1") (pintype "passive"))
      (node (ref "R14") (pin "1") (pinfunction "1_1") (pintype "passive"))
      (node (ref "R17") (pin "2") (pinfunction "2_2") (pintype "passive"))
      (node (ref "U$4") (pin "2") (pinfunction "S_2") (pintype "passive"))
      (node (ref "X1") (pin "1") (pinfunction "1_1") (pintype "passive"))
    )
    (net (code "53") (name "WS2812B_DATA") (class "Default")
      (node (ref "J2") (pin "2") (pinfunction "2_2") (pintype "passive"))
      (node (ref "R27") (pin "2") (pinfunction "2_2") (pintype "passive"))
      (node (ref "U1") (pin "24") (pinfunction "IO2_24") (pintype "bidirectional"))
    )
    (net (code "54") (name "unconnected-(DS1-DB0-PadP$7)") (class "Default")
      (node (ref "DS1") (pin "P$7") (pinfunction "DB0_P$7") (pintype "bidirectional"))
    )
    (net (code "55") (name "unconnected-(DS1-DB1-PadP$8)") (class "Default")
      (node (ref "DS1") (pin "P$8") (pinfunction "DB1_P$8") (pintype "bidirectional"))
    )
    (net (code "56") (name "unconnected-(DS1-DB2-PadP$9)") (class "Default")
      (node (ref "DS1") (pin "P$9") (pinfunction "DB2_P$9") (pintype "bidirectional"))
    )
    (net (code "57") (name "unconnected-(DS1-DB3-PadP$10)") (class "Default")
      (node (ref "DS1") (pin "P$10") (pinfunction "DB3_P$10") (pintype "bidirectional"))
    )
    (net (code "58") (name "unconnected-(DS1-MH1-Pad17)") (class "Default")
      (node (ref "DS1") (pin "17") (pinfunction "MH1_17") (pintype "bidirectional"))
    )
    (net (code "59") (name "unconnected-(DS1-MH2-Pad18)") (class "Default")
      (node (ref "DS1") (pin "18") (pinfunction "MH2_18") (pintype "bidirectional"))
    )
    (net (code "60") (name "unconnected-(DS1-MH3-Pad19)") (class "Default")
      (node (ref "DS1") (pin "19") (pinfunction "MH3_19") (pintype "bidirectional"))
    )
    (net (code "61") (name "unconnected-(DS1-MH4-Pad21)") (class "Default")
      (node (ref "DS1") (pin "21") (pinfunction "MH4_21") (pintype "bidirectional"))
    )
    (net (code "62") (name "unconnected-(IC1-PadMH1)") (class "Default")
      (node (ref "IC1") (pin "MH1") (pinfunction "MH1_MH1") (pintype "bidirectional"))
    )
    (net (code "63") (name "unconnected-(IC1-PadMH2)") (class "Default")
      (node (ref "IC1") (pin "MH2") (pinfunction "MH2_MH2") (pintype "bidirectional"))
    )
    (net (code "64") (name "unconnected-(IC2-+INB-Pad5)") (class "Default")
      (node (ref "IC2") (pin "5") (pinfunction "+INB_5") (pintype "bidirectional"))
    )
    (net (code "65") (name "unconnected-(IC2--INB-Pad6)") (class "Default")
      (node (ref "IC2") (pin "6") (pinfunction "-INB_6") (pintype "bidirectional"))
    )
    (net (code "66") (name "unconnected-(IC2-OUTB-Pad7)") (class "Default")
      (node (ref "IC2") (pin "7") (pinfunction "OUTB_7") (pintype "bidirectional"))
    )
    (net (code "67") (name "unconnected-(U$7-1-PadP$1)") (class "Default")
      (node (ref "U$7") (pin "P$1") (pinfunction "1_P$1") (pintype "passive"))
    )
    (net (code "68") (name "unconnected-(U1-SCK{slash}CLK-Pad20)") (class "Default")
      (node (ref "U1") (pin "20") (pinfunction "SCK/CLK_20") (pintype "bidirectional"))
    )
    (net (code "69") (name "unconnected-(U1-SCS{slash}CMD-Pad19)") (class "Default")
      (node (ref "U1") (pin "19") (pinfunction "SCS/CMD_19") (pintype "bidirectional"))
    )
    (net (code "70") (name "unconnected-(U1-SDI{slash}SD1-Pad22)") (class "Default")
      (node (ref "U1") (pin "22") (pinfunction "SDI/SD1_22") (pintype "bidirectional"))
    )
    (net (code "71") (name "unconnected-(U1-SDO{slash}SD0-Pad21)") (class "Default")
      (node (ref "U1") (pin "21") (pinfunction "SDO/SD0_21") (pintype "bidirectional"))
    )
    (net (code "72") (name "unconnected-(U1-SHD{slash}SD2-Pad17)") (class "Default")
      (node (ref "U1") (pin "17") (pinfunction "SHD/SD2_17") (pintype "bidirectional"))
    )
    (net (code "73") (name "unconnected-(U1-SWP{slash}SD3-Pad18)") (class "Default")
      (node (ref "U1") (pin "18") (pinfunction "SWP/SD3_18") (pintype "bidirectional"))
    )
  )
)
